# NJM2936_MAU106_PSU.net
KiCad netlist of a schematic drawn in EAGLE
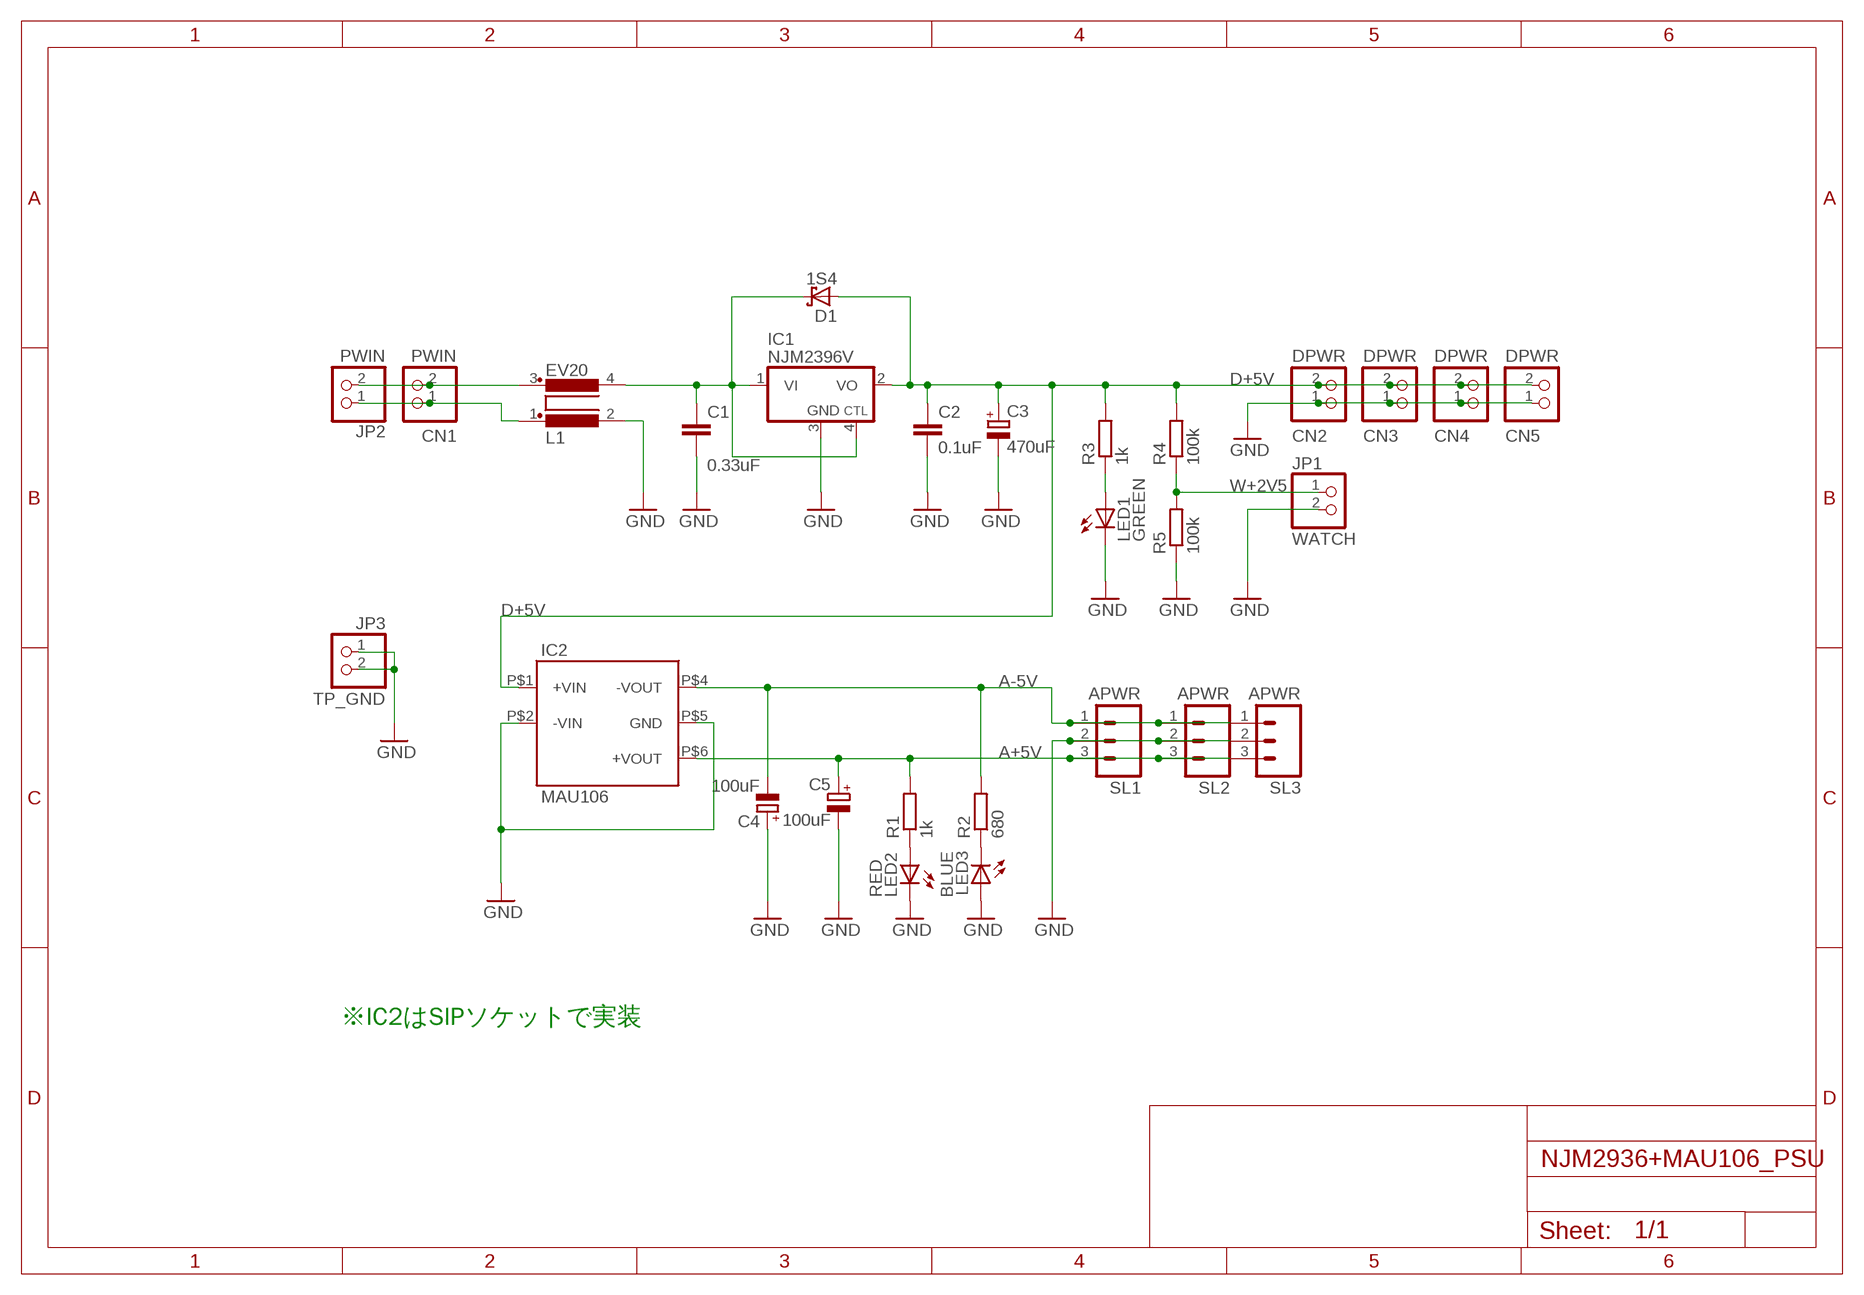
[diagram p0: schematic, sheet 1]

(export (version "E")
  (design (tool "Eeschema 10.0.6"))
  (components
    (comp (ref "C1")
      (value "0.33uF")
      (footprint "eagle-import:C050-030X075")
      (libsource (lib "eagle-import") (part "C-EU050-030X075"))
    )
    (comp (ref "C2")
      (value "0.1uF")
      (footprint "eagle-import:C025-024X044")
      (libsource (lib "eagle-import") (part "C-EU025-024X044"))
    )
    (comp (ref "C3")
      (value "470uF")
      (footprint "eagle-import:SANYO-OSCON_F13")
      (libsource (lib "eagle-import") (part "CPOL-EUSANYO_F13"))
    )
    (comp (ref "C4")
      (value "100uF")
      (footprint "eagle-import:SANYO-OSCON_C6")
      (libsource (lib "eagle-import") (part "CPOL-EUSANYO_C6"))
    )
    (comp (ref "C5")
      (value "100uF")
      (footprint "eagle-import:SANYO-OSCON_C6")
      (libsource (lib "eagle-import") (part "CPOL-EUSANYO_C6"))
    )
    (comp (ref "CN1")
      (value "PWIN")
      (footprint "eagle-import:B2B-XH-A")
      (libsource (lib "eagle-import") (part "B2B-XH-A"))
    )
    (comp (ref "CN2")
      (value "DPWR")
      (footprint "eagle-import:B2B-XH-A")
      (libsource (lib "eagle-import") (part "B2B-XH-A"))
    )
    (comp (ref "CN3")
      (value "DPWR")
      (footprint "eagle-import:B2B-XH-A")
      (libsource (lib "eagle-import") (part "B2B-XH-A"))
    )
    (comp (ref "CN4")
      (value "DPWR")
      (footprint "eagle-import:B2B-XH-A")
      (libsource (lib "eagle-import") (part "B2B-XH-A"))
    )
    (comp (ref "CN5")
      (value "DPWR")
      (footprint "eagle-import:B2B-XH-A")
      (libsource (lib "eagle-import") (part "B2B-XH-A"))
    )
    (comp (ref "D1")
      (value "1S4")
      (footprint "eagle-import:DO35-7")
      (libsource (lib "eagle-import") (part "SCHOTTKY-DIODEDO35-7"))
    )
    (comp (ref "IC1")
      (value "NJM2396V")
      (footprint "eagle-import:TO220-4V")
      (libsource (lib "eagle-import") (part "NJM2396V"))
    )
    (comp (ref "IC2")
      (value "MAU106")
      (footprint "eagle-import:MAU106")
      (libsource (lib "eagle-import") (part "MAU106"))
    )
    (comp (ref "JP1")
      (value "WATCH")
      (footprint "eagle-import:1X02")
      (libsource (lib "eagle-import") (part "PINHD-1X2"))
    )
    (comp (ref "JP2")
      (value "PWIN")
      (footprint "eagle-import:1X02")
      (libsource (lib "eagle-import") (part "PINHD-1X2"))
    )
    (comp (ref "JP3")
      (value "TP_GND")
      (footprint "eagle-import:1X02")
      (libsource (lib "eagle-import") (part "PINHD-1X2"))
    )
    (comp (ref "L1")
      (value "EV20")
      (footprint "eagle-import:EV20")
      (libsource (lib "eagle-import") (part "EV20"))
    )
    (comp (ref "LED1")
      (value "GREEN")
      (footprint "eagle-import:LED3MM")
      (libsource (lib "eagle-import") (part "LED3MM"))
    )
    (comp (ref "LED2")
      (value "RED")
      (footprint "eagle-import:LED3MM")
      (libsource (lib "eagle-import") (part "LED3MM"))
    )
    (comp (ref "LED3")
      (value "BLUE")
      (footprint "eagle-import:LED3MM")
      (libsource (lib "eagle-import") (part "LED3MM"))
    )
    (comp (ref "R1")
      (value "1k")
      (footprint "eagle-import:0207_7")
      (libsource (lib "eagle-import") (part "R-EU_0207/7"))
    )
    (comp (ref "R2")
      (value "680")
      (footprint "eagle-import:0207_7")
      (libsource (lib "eagle-import") (part "R-EU_0207/7"))
    )
    (comp (ref "R3")
      (value "1k")
      (footprint "eagle-import:0207_7")
      (libsource (lib "eagle-import") (part "R-EU_0207/7"))
    )
    (comp (ref "R4")
      (value "100k")
      (footprint "eagle-import:0207_7")
      (libsource (lib "eagle-import") (part "R-EU_0207/7"))
    )
    (comp (ref "R5")
      (value "100k")
      (footprint "eagle-import:0207_7")
      (libsource (lib "eagle-import") (part "R-EU_0207/7"))
    )
    (comp (ref "SL1")
      (value "APWR")
      (footprint "eagle-import:03P")
      (libsource (lib "eagle-import") (part "M03"))
    )
    (comp (ref "SL2")
      (value "APWR")
      (footprint "eagle-import:03P")
      (libsource (lib "eagle-import") (part "M03"))
    )
    (comp (ref "SL3")
      (value "APWR")
      (footprint "eagle-import:03P")
      (libsource (lib "eagle-import") (part "M03"))
    )
  )
  (nets
    (net (code "1") (name "/A+5V") (class "Default")
      (node (ref "C5") (pin "+") (pinfunction "+_+") (pintype "passive"))
      (node (ref "IC2") (pin "P$6") (pinfunction "+VOUT_P$6") (pintype "output"))
      (node (ref "R1") (pin "2") (pinfunction "2_2") (pintype "passive"))
      (node (ref "SL1") (pin "3") (pinfunction "3_3") (pintype "passive"))
      (node (ref "SL2") (pin "3") (pinfunction "3_3") (pintype "passive"))
      (node (ref "SL3") (pin "3") (pinfunction "3_3") (pintype "passive"))
    )
    (net (code "2") (name "/A-5V") (class "Default")
      (node (ref "C4") (pin "-") (pinfunction "-_-") (pintype "passive"))
      (node (ref "IC2") (pin "P$4") (pinfunction "-VOUT_P$4") (pintype "output"))
      (node (ref "R2") (pin "2") (pinfunction "2_2") (pintype "passive"))
      (node (ref "SL1") (pin "1") (pinfunction "1_1") (pintype "passive"))
      (node (ref "SL2") (pin "1") (pinfunction "1_1") (pintype "passive"))
      (node (ref "SL3") (pin "1") (pinfunction "1_1") (pintype "passive"))
    )
    (net (code "3") (name "/D+5V") (class "Default")
      (node (ref "C2") (pin "1") (pinfunction "1_1") (pintype "passive"))
      (node (ref "C3") (pin "+") (pinfunction "+_+") (pintype "passive"))
      (node (ref "CN2") (pin "2") (pinfunction "2_2") (pintype "passive"))
      (node (ref "CN3") (pin "2") (pinfunction "2_2") (pintype "passive"))
      (node (ref "CN4") (pin "2") (pinfunction "2_2") (pintype "passive"))
      (node (ref "CN5") (pin "2") (pinfunction "2_2") (pintype "passive"))
      (node (ref "D1") (pin "A") (pinfunction "A_A") (pintype "passive"))
      (node (ref "IC1") (pin "2") (pinfunction "VO_2") (pintype "output"))
      (node (ref "IC2") (pin "P$1") (pinfunction "+VIN_P$1") (pintype "input"))
      (node (ref "R3") (pin "2") (pinfunction "2_2") (pintype "passive"))
      (node (ref "R4") (pin "2") (pinfunction "2_2") (pintype "passive"))
    )
    (net (code "4") (name "/W+2V5") (class "Default")
      (node (ref "JP1") (pin "1") (pinfunction "1_1") (pintype "passive"))
      (node (ref "R4") (pin "1") (pinfunction "1_1") (pintype "passive"))
      (node (ref "R5") (pin "2") (pinfunction "2_2") (pintype "passive"))
    )
    (net (code "5") (name "GND") (class "Default")
      (node (ref "C1") (pin "2") (pinfunction "2_2") (pintype "passive"))
      (node (ref "C2") (pin "2") (pinfunction "2_2") (pintype "passive"))
      (node (ref "C3") (pin "-") (pinfunction "-_-") (pintype "passive"))
      (node (ref "C4") (pin "+") (pinfunction "+_+") (pintype "passive"))
      (node (ref "C5") (pin "-") (pinfunction "-_-") (pintype "passive"))
      (node (ref "CN2") (pin "1") (pinfunction "1_1") (pintype "passive"))
      (node (ref "CN3") (pin "1") (pinfunction "1_1") (pintype "passive"))
      (node (ref "CN4") (pin "1") (pinfunction "1_1") (pintype "passive"))
      (node (ref "CN5") (pin "1") (pinfunction "1_1") (pintype "passive"))
      (node (ref "IC1") (pin "3") (pinfunction "GND_3") (pintype "power_in"))
      (node (ref "IC2") (pin "P$2") (pinfunction "-VIN_P$2") (pintype "input"))
      (node (ref "IC2") (pin "P$5") (pinfunction "GND_P$5") (pintype "power_in"))
      (node (ref "JP1") (pin "2") (pinfunction "2_2") (pintype "passive"))
      (node (ref "JP3") (pin "1") (pinfunction "1_1") (pintype "passive"))
      (node (ref "JP3") (pin "2") (pinfunction "2_2") (pintype "passive"))
      (node (ref "L1") (pin "2") (pinfunction "2_2") (pintype "passive"))
      (node (ref "LED1") (pin "K") (pinfunction "C_K") (pintype "passive"))
      (node (ref "LED2") (pin "K") (pinfunction "C_K") (pintype "passive"))
      (node (ref "LED3") (pin "A") (pinfunction "A_A") (pintype "passive"))
      (node (ref "R5") (pin "1") (pinfunction "1_1") (pintype "passive"))
      (node (ref "SL1") (pin "2") (pinfunction "2_2") (pintype "passive"))
      (node (ref "SL2") (pin "2") (pinfunction "2_2") (pintype "passive"))
      (node (ref "SL3") (pin "2") (pinfunction "2_2") (pintype "passive"))
    )
    (net (code "6") (name "Net-(CN1-Pad1)") (class "Default")
      (node (ref "CN1") (pin "1") (pinfunction "1_1") (pintype "passive"))
      (node (ref "JP2") (pin "1") (pinfunction "1_1") (pintype "passive"))
      (node (ref "L1") (pin "1") (pinfunction "1_1") (pintype "passive"))
    )
    (net (code "7") (name "Net-(CN1-Pad2)") (class "Default")
      (node (ref "CN1") (pin "2") (pinfunction "2_2") (pintype "passive"))
      (node (ref "JP2") (pin "2") (pinfunction "2_2") (pintype "passive"))
      (node (ref "L1") (pin "3") (pinfunction "3_3") (pintype "passive"))
    )
    (net (code "8") (name "Net-(IC1-CTL)") (class "Default")
      (node (ref "C1") (pin "1") (pinfunction "1_1") (pintype "passive"))
      (node (ref "D1") (pin "C") (pinfunction "C_C") (pintype "passive"))
      (node (ref "IC1") (pin "1") (pinfunction "VI_1") (pintype "input"))
      (node (ref "IC1") (pin "4") (pinfunction "CTL_4") (pintype "input"))
      (node (ref "L1") (pin "4") (pinfunction "4_4") (pintype "passive"))
    )
    (net (code "9") (name "Net-(LED1-PadA)") (class "Default")
      (node (ref "LED1") (pin "A") (pinfunction "A_A") (pintype "passive"))
      (node (ref "R3") (pin "1") (pinfunction "1_1") (pintype "passive"))
    )
    (net (code "10") (name "Net-(LED2-PadA)") (class "Default")
      (node (ref "LED2") (pin "A") (pinfunction "A_A") (pintype "passive"))
      (node (ref "R1") (pin "1") (pinfunction "1_1") (pintype "passive"))
    )
    (net (code "11") (name "Net-(LED3-C)") (class "Default")
      (node (ref "LED3") (pin "K") (pinfunction "C_K") (pintype "passive"))
      (node (ref "R2") (pin "1") (pinfunction "1_1") (pintype "passive"))
    )
  )
)
